# S7CAS-PLEIADES-CARTE-MERE_P02_USB.net
KiCad netlist of a schematic drawn in Altium Designer
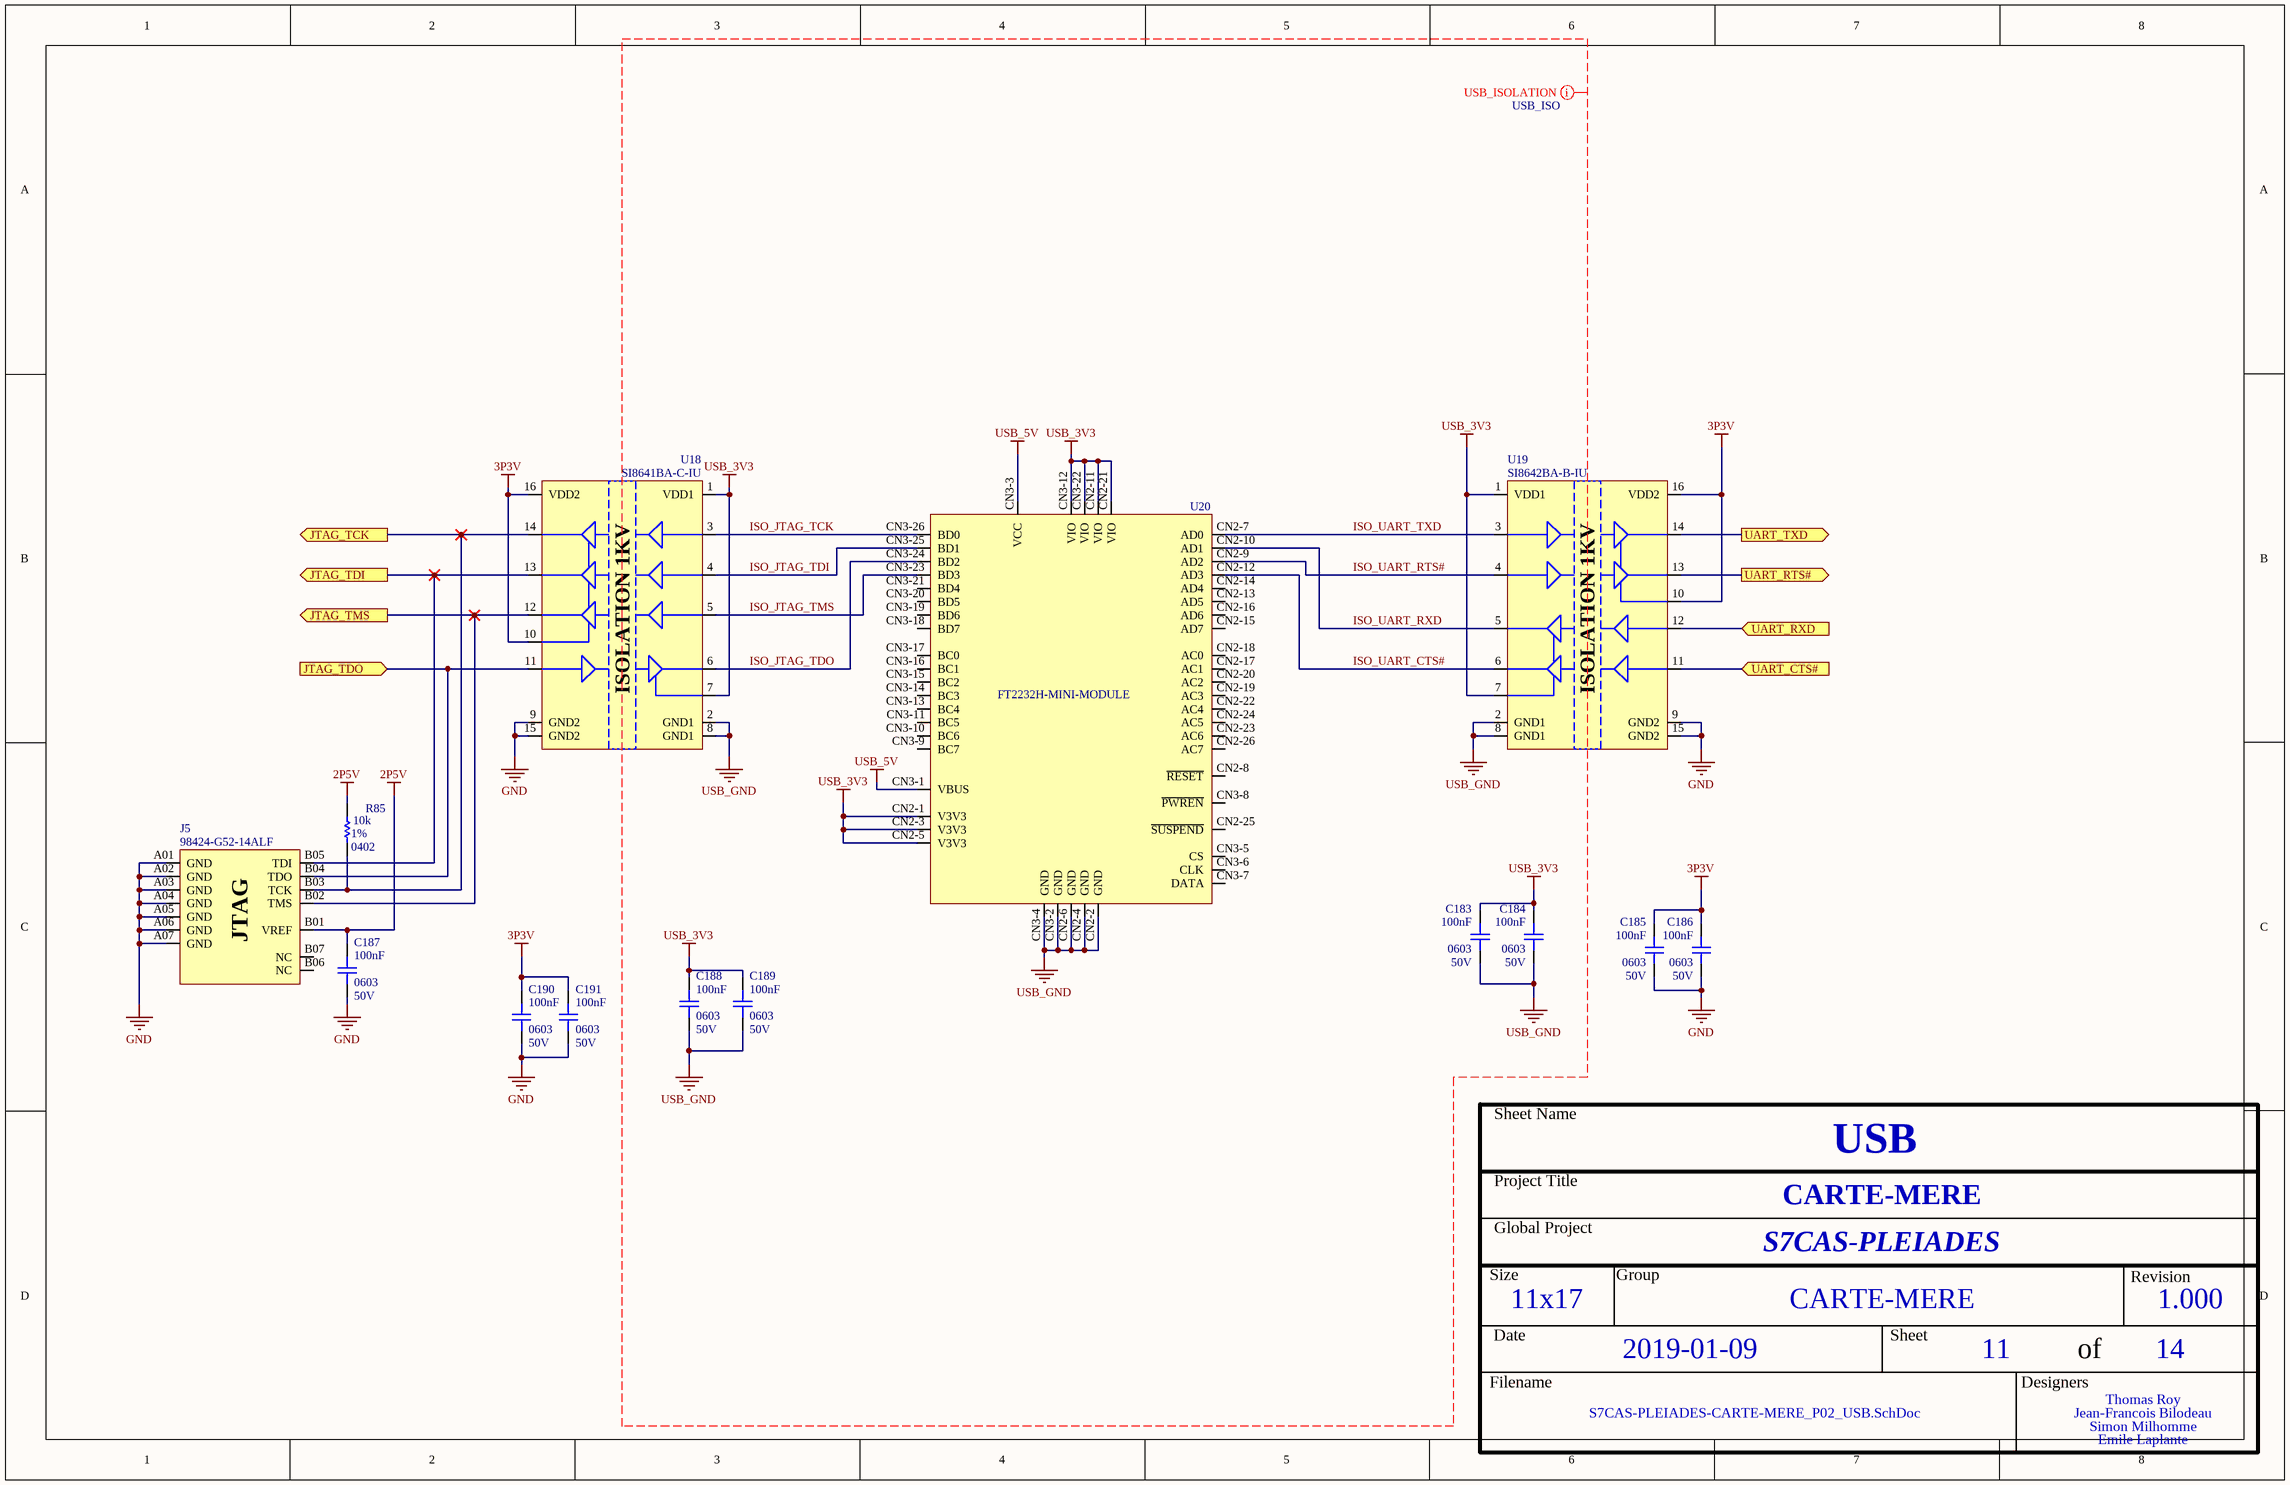
[diagram p0: S7CAS-PLEIADES-CARTE-MERE_P02_USB.SchDoc]

(export (version "E")
  (design (tool "Eeschema 10.0.6"))
  (components
    (comp (ref "C183")
      (value "100nF")
      (footprint "CAP_0603")
      (description "CAP - 0603")
      (fields
        (field (name "VOLTAGE") "50V")
        (field (name "PACKAGE") "0603")
        (field (name "CREATEDBY") "Jonathan Bouchard")
      )
      (libsource (lib "S7CAS_Lib2019_REV1_00") (part "CAP - 0603"))
    )
    (comp (ref "C184")
      (value "100nF")
      (footprint "CAP_0603")
      (description "CAP - 0603")
      (fields
        (field (name "VOLTAGE") "50V")
        (field (name "PACKAGE") "0603")
        (field (name "CREATEDBY") "Jonathan Bouchard")
      )
      (libsource (lib "S7CAS_Lib2019_REV1_00") (part "CAP - 0603"))
    )
    (comp (ref "C185")
      (value "100nF")
      (footprint "CAP_0603")
      (description "CAP - 0603")
      (fields
        (field (name "VOLTAGE") "50V")
        (field (name "PACKAGE") "0603")
        (field (name "CREATEDBY") "Jonathan Bouchard")
      )
      (libsource (lib "S7CAS_Lib2019_REV1_00") (part "CAP - 0603"))
    )
    (comp (ref "C186")
      (value "100nF")
      (footprint "CAP_0603")
      (description "CAP - 0603")
      (fields
        (field (name "VOLTAGE") "50V")
        (field (name "PACKAGE") "0603")
        (field (name "CREATEDBY") "Jonathan Bouchard")
      )
      (libsource (lib "S7CAS_Lib2019_REV1_00") (part "CAP - 0603"))
    )
    (comp (ref "C187")
      (value "100nF")
      (footprint "CAP_0603")
      (description "CAP - 0603")
      (fields
        (field (name "VOLTAGE") "50V")
        (field (name "PACKAGE") "0603")
        (field (name "CREATEDBY") "Jonathan Bouchard")
      )
      (libsource (lib "S7CAS_Lib2019_REV1_00") (part "CAP - 0603"))
    )
    (comp (ref "C188")
      (value "100nF")
      (footprint "CAP_0603")
      (description "CAP - 0603")
      (fields
        (field (name "VOLTAGE") "50V")
        (field (name "PACKAGE") "0603")
        (field (name "CREATEDBY") "Jonathan Bouchard")
      )
      (libsource (lib "S7CAS_Lib2019_REV1_00") (part "CAP - 0603"))
    )
    (comp (ref "C189")
      (value "100nF")
      (footprint "CAP_0603")
      (description "CAP - 0603")
      (fields
        (field (name "VOLTAGE") "50V")
        (field (name "PACKAGE") "0603")
        (field (name "CREATEDBY") "Jonathan Bouchard")
      )
      (libsource (lib "S7CAS_Lib2019_REV1_00") (part "CAP - 0603"))
    )
    (comp (ref "C190")
      (value "100nF")
      (footprint "CAP_0603")
      (description "CAP - 0603")
      (fields
        (field (name "VOLTAGE") "50V")
        (field (name "PACKAGE") "0603")
        (field (name "CREATEDBY") "Jonathan Bouchard")
      )
      (libsource (lib "S7CAS_Lib2019_REV1_00") (part "CAP - 0603"))
    )
    (comp (ref "C191")
      (value "100nF")
      (footprint "CAP_0603")
      (description "CAP - 0603")
      (fields
        (field (name "VOLTAGE") "50V")
        (field (name "PACKAGE") "0603")
        (field (name "CREATEDBY") "Jonathan Bouchard")
      )
      (libsource (lib "S7CAS_Lib2019_REV1_00") (part "CAP - 0603"))
    )
    (comp (ref "J5")
      (value "98424-G52-14ALF")
      (footprint "CON_JTAG_98424-G52-14ALF")
      (description "CONN -  JTAG HEADER XILINX - 14-SMD")
      (fields (field (name "MFG") "Amphenol") (field (name "CREATEDBY") "Jonathan Bouchard"))
      (libsource (lib "S7CAS_Lib2019_REV1_00") (part "CONN_JTAG_98424-G52-14ALF"))
    )
    (comp (ref "R85")
      (value "10k")
      (footprint "RES_0402")
      (description "RES - 0402")
      (fields
        (field (name "VOLTAGE") "50V")
        (field (name "POWER") "1/16W")
        (field (name "PACKAGE") "0402")
        (field (name "PRECISION") "1%")
        (field (name "CREATEDBY") "Jonathan Bouchard")
      )
      (libsource (lib "S7CAS_Lib2019_REV1_00") (part "RES - 0402"))
    )
    (comp (ref "U18")
      (value "SI8641BA-C-IU")
      (footprint "ISO_SI8642BA-B-IU")
      (description "ISO - DIGITAL ISOLATOR 1KV 4CH 3:1 GEN PURP -  SOP-16")
      (fields
        (field (name "VOLTAGE") "2.5 V ~ 5.5 V")
        (field (name "MFG") "Silicon Labs")
        (field (name "CREATEDBY") "Jonathan Bouchard")
      )
      (libsource (lib "S7CAS_Lib2019_REV1_00") (part "ISO_SI8641BA-C-IU"))
    )
    (comp (ref "U19")
      (value "SI8642BA-B-IU")
      (footprint "ISO_SI8642BA-B-IU")
      (description "ISO - DIGITAL ISOLATOR 1KV 4CH 2:2 GEN PURP -  SOP-16")
      (fields
        (field (name "VOLTAGE") "2.5 V ~ 5.5 V")
        (field (name "MFG") "Silicon Labs")
        (field (name "CREATEDBY") "Jonathan Bouchard")
      )
      (libsource (lib "S7CAS_Lib2019_REV1_00") (part "ISO_SI8642BA-B-IU"))
    )
    (comp (ref "U20")
      (value "FT2232H-MINI-MODULE")
      (footprint "COM_USB_FT2232H-MINI-MODULE")
      (description "COM - USB FTDI FT2232H Mini-Module - TH")
      (fields (field (name "MFG") "Micrel") (field (name "CREATEDBY") "Jonathan Bouchard"))
      (libsource (lib "S7CAS_Lib2019_REV1_00") (part "COM_USB_FT2232H-MINI-MODULE"))
    )
  )
  (nets
    (net (code "1") (name "/ISO_JTAG_TCK") (class "Default")
      (node (ref "U18") (pin "3") (pinfunction "A1_3") (pintype "passive"))
      (node (ref "U20") (pin "CN3-26") (pinfunction "BD0_CN3-26") (pintype "passive"))
    )
    (net (code "2") (name "/ISO_JTAG_TDI") (class "Default")
      (node (ref "U18") (pin "4") (pinfunction "A2_4") (pintype "passive"))
      (node (ref "U20") (pin "CN3-25") (pinfunction "BD1_CN3-25") (pintype "passive"))
    )
    (net (code "3") (name "/ISO_JTAG_TDO") (class "Default")
      (node (ref "U18") (pin "6") (pinfunction "A4_6") (pintype "passive"))
      (node (ref "U20") (pin "CN3-24") (pinfunction "BD2_CN3-24") (pintype "passive"))
    )
    (net (code "4") (name "/ISO_JTAG_TMS") (class "Default")
      (node (ref "U18") (pin "5") (pinfunction "A3_5") (pintype "passive"))
      (node (ref "U20") (pin "CN3-23") (pinfunction "BD3_CN3-23") (pintype "passive"))
    )
    (net (code "5") (name "/ISO_UART_CTS#") (class "Default")
      (node (ref "U19") (pin "6") (pinfunction "A4_6") (pintype "passive"))
      (node (ref "U20") (pin "CN2-12") (pinfunction "AD3_CN2-12") (pintype "passive"))
    )
    (net (code "6") (name "/ISO_UART_RTS#") (class "Default")
      (node (ref "U19") (pin "4") (pinfunction "A2_4") (pintype "passive"))
      (node (ref "U20") (pin "CN2-9") (pinfunction "AD2_CN2-9") (pintype "passive"))
    )
    (net (code "7") (name "/ISO_UART_RXD") (class "Default")
      (node (ref "U19") (pin "5") (pinfunction "A3_5") (pintype "passive"))
      (node (ref "U20") (pin "CN2-10") (pinfunction "AD1_CN2-10") (pintype "passive"))
    )
    (net (code "8") (name "/ISO_UART_TXD") (class "Default")
      (node (ref "U19") (pin "3") (pinfunction "A1_3") (pintype "passive"))
      (node (ref "U20") (pin "CN2-7") (pinfunction "AD0_CN2-7") (pintype "passive"))
    )
    (net (code "9") (name "/JTAG_TCK") (class "Default")
      (node (ref "J5") (pin "B03") (pinfunction "TCK_B03") (pintype "passive"))
      (node (ref "R85") (pin "1") (pinfunction "1_1") (pintype "passive"))
      (node (ref "U18") (pin "14") (pinfunction "B1_14") (pintype "passive"))
    )
    (net (code "10") (name "/JTAG_TDI") (class "Default")
      (node (ref "J5") (pin "B05") (pinfunction "TDI_B05") (pintype "passive"))
      (node (ref "U18") (pin "13") (pinfunction "B2_13") (pintype "passive"))
    )
    (net (code "11") (name "/JTAG_TDO") (class "Default")
      (node (ref "J5") (pin "B04") (pinfunction "TDO_B04") (pintype "passive"))
      (node (ref "U18") (pin "11") (pinfunction "B4_11") (pintype "passive"))
    )
    (net (code "12") (name "/JTAG_TMS") (class "Default")
      (node (ref "J5") (pin "B02") (pinfunction "TMS_B02") (pintype "passive"))
      (node (ref "U18") (pin "12") (pinfunction "B3_12") (pintype "passive"))
    )
    (net (code "13") (name "/UART_CTS#") (class "Default")
      (node (ref "U19") (pin "11") (pinfunction "B4_11") (pintype "passive"))
    )
    (net (code "14") (name "/UART_RTS#") (class "Default")
      (node (ref "U19") (pin "13") (pinfunction "B2_13") (pintype "passive"))
    )
    (net (code "15") (name "/UART_RXD") (class "Default")
      (node (ref "U19") (pin "12") (pinfunction "B3_12") (pintype "passive"))
    )
    (net (code "16") (name "/UART_TXD") (class "Default")
      (node (ref "U19") (pin "14") (pinfunction "B1_14") (pintype "passive"))
    )
    (net (code "17") (name "2P5V") (class "Default")
      (node (ref "C187") (pin "2") (pinfunction "2_2") (pintype "passive"))
      (node (ref "J5") (pin "B01") (pinfunction "VREF_B01") (pintype "passive"))
      (node (ref "R85") (pin "2") (pinfunction "2_2") (pintype "passive"))
    )
    (net (code "18") (name "3P3V") (class "Default")
      (node (ref "C185") (pin "2") (pinfunction "2_2") (pintype "passive"))
      (node (ref "C186") (pin "2") (pinfunction "2_2") (pintype "passive"))
      (node (ref "C190") (pin "2") (pinfunction "2_2") (pintype "passive"))
      (node (ref "C191") (pin "2") (pinfunction "2_2") (pintype "passive"))
      (node (ref "U18") (pin "10") (pinfunction "EN2_10") (pintype "passive"))
      (node (ref "U18") (pin "16") (pinfunction "VDD2_16") (pintype "power_in"))
      (node (ref "U19") (pin "10") (pinfunction "EN2_10") (pintype "passive"))
      (node (ref "U19") (pin "16") (pinfunction "VDD2_16") (pintype "power_in"))
    )
    (net (code "19") (name "GND") (class "Default")
      (node (ref "C185") (pin "1") (pinfunction "1_1") (pintype "passive"))
      (node (ref "C186") (pin "1") (pinfunction "1_1") (pintype "passive"))
      (node (ref "C187") (pin "1") (pinfunction "1_1") (pintype "passive"))
      (node (ref "C190") (pin "1") (pinfunction "1_1") (pintype "passive"))
      (node (ref "C191") (pin "1") (pinfunction "1_1") (pintype "passive"))
      (node (ref "J5") (pin "A01") (pinfunction "GND_A01") (pintype "passive"))
      (node (ref "J5") (pin "A02") (pinfunction "GND_A02") (pintype "passive"))
      (node (ref "J5") (pin "A03") (pinfunction "GND_A03") (pintype "passive"))
      (node (ref "J5") (pin "A04") (pinfunction "GND_A04") (pintype "passive"))
      (node (ref "J5") (pin "A05") (pinfunction "GND_A05") (pintype "passive"))
      (node (ref "J5") (pin "A06") (pinfunction "GND_A06") (pintype "passive"))
      (node (ref "J5") (pin "A07") (pinfunction "GND_A07") (pintype "passive"))
      (node (ref "U18") (pin "15") (pinfunction "GND2_15") (pintype "passive"))
      (node (ref "U18") (pin "9") (pinfunction "GND2_9") (pintype "passive"))
      (node (ref "U19") (pin "15") (pinfunction "GND2_15") (pintype "passive"))
      (node (ref "U19") (pin "9") (pinfunction "GND2_9") (pintype "passive"))
    )
    (net (code "20") (name "USB_3V3") (class "Default")
      (node (ref "C183") (pin "2") (pinfunction "2_2") (pintype "passive"))
      (node (ref "C184") (pin "2") (pinfunction "2_2") (pintype "passive"))
      (node (ref "C188") (pin "2") (pinfunction "2_2") (pintype "passive"))
      (node (ref "C189") (pin "2") (pinfunction "2_2") (pintype "passive"))
      (node (ref "U18") (pin "1") (pinfunction "VDD1_1") (pintype "power_in"))
      (node (ref "U18") (pin "7") (pinfunction "EN1_7") (pintype "passive"))
      (node (ref "U19") (pin "1") (pinfunction "VDD1_1") (pintype "power_in"))
      (node (ref "U19") (pin "7") (pinfunction "EN1_7") (pintype "passive"))
      (node (ref "U20") (pin "CN2-1") (pinfunction "V3V3_CN2-1") (pintype "power_in"))
      (node (ref "U20") (pin "CN2-11") (pinfunction "VIO_CN2-11") (pintype "passive"))
      (node (ref "U20") (pin "CN2-21") (pinfunction "VIO_CN2-21") (pintype "passive"))
      (node (ref "U20") (pin "CN2-3") (pinfunction "V3V3_CN2-3") (pintype "power_in"))
      (node (ref "U20") (pin "CN2-5") (pinfunction "V3V3_CN2-5") (pintype "power_in"))
      (node (ref "U20") (pin "CN3-12") (pinfunction "VIO_CN3-12") (pintype "passive"))
      (node (ref "U20") (pin "CN3-22") (pinfunction "VIO_CN3-22") (pintype "passive"))
    )
    (net (code "21") (name "USB_5V") (class "Default")
      (node (ref "U20") (pin "CN3-1") (pinfunction "VBUS_CN3-1") (pintype "passive"))
      (node (ref "U20") (pin "CN3-3") (pinfunction "VCC_CN3-3") (pintype "power_in"))
    )
    (net (code "22") (name "USB_GND") (class "Default")
      (node (ref "C183") (pin "1") (pinfunction "1_1") (pintype "passive"))
      (node (ref "C184") (pin "1") (pinfunction "1_1") (pintype "passive"))
      (node (ref "C188") (pin "1") (pinfunction "1_1") (pintype "passive"))
      (node (ref "C189") (pin "1") (pinfunction "1_1") (pintype "passive"))
      (node (ref "U18") (pin "2") (pinfunction "GND1_2") (pintype "passive"))
      (node (ref "U18") (pin "8") (pinfunction "GND1_8") (pintype "passive"))
      (node (ref "U19") (pin "2") (pinfunction "GND1_2") (pintype "passive"))
      (node (ref "U19") (pin "8") (pinfunction "GND1_8") (pintype "passive"))
      (node (ref "U20") (pin "CN2-2") (pinfunction "GND_CN2-2") (pintype "passive"))
      (node (ref "U20") (pin "CN2-4") (pinfunction "GND_CN2-4") (pintype "passive"))
      (node (ref "U20") (pin "CN2-6") (pinfunction "GND_CN2-6") (pintype "passive"))
      (node (ref "U20") (pin "CN3-2") (pinfunction "GND_CN3-2") (pintype "passive"))
      (node (ref "U20") (pin "CN3-4") (pinfunction "GND_CN3-4") (pintype "passive"))
    )
    (net (code "23") (name "unconnected-(J5-NC-PadB06)") (class "Default")
      (node (ref "J5") (pin "B06") (pinfunction "NC_B06") (pintype "passive"))
    )
    (net (code "24") (name "unconnected-(J5-NC-PadB07)") (class "Default")
      (node (ref "J5") (pin "B07") (pinfunction "NC_B07") (pintype "passive"))
    )
    (net (code "25") (name "unconnected-(U20-AC0-PadCN2-18)") (class "Default")
      (node (ref "U20") (pin "CN2-18") (pinfunction "AC0_CN2-18") (pintype "passive"))
    )
    (net (code "26") (name "unconnected-(U20-AC1-PadCN2-17)") (class "Default")
      (node (ref "U20") (pin "CN2-17") (pinfunction "AC1_CN2-17") (pintype "passive"))
    )
    (net (code "27") (name "unconnected-(U20-AC2-PadCN2-20)") (class "Default")
      (node (ref "U20") (pin "CN2-20") (pinfunction "AC2_CN2-20") (pintype "passive"))
    )
    (net (code "28") (name "unconnected-(U20-AC3-PadCN2-19)") (class "Default")
      (node (ref "U20") (pin "CN2-19") (pinfunction "AC3_CN2-19") (pintype "passive"))
    )
    (net (code "29") (name "unconnected-(U20-AC4-PadCN2-22)") (class "Default")
      (node (ref "U20") (pin "CN2-22") (pinfunction "AC4_CN2-22") (pintype "passive"))
    )
    (net (code "30") (name "unconnected-(U20-AC5-PadCN2-24)") (class "Default")
      (node (ref "U20") (pin "CN2-24") (pinfunction "AC5_CN2-24") (pintype "passive"))
    )
    (net (code "31") (name "unconnected-(U20-AC6-PadCN2-23)") (class "Default")
      (node (ref "U20") (pin "CN2-23") (pinfunction "AC6_CN2-23") (pintype "passive"))
    )
    (net (code "32") (name "unconnected-(U20-AC7-PadCN2-26)") (class "Default")
      (node (ref "U20") (pin "CN2-26") (pinfunction "AC7_CN2-26") (pintype "passive"))
    )
    (net (code "33") (name "unconnected-(U20-AD4-PadCN2-14)") (class "Default")
      (node (ref "U20") (pin "CN2-14") (pinfunction "AD4_CN2-14") (pintype "passive"))
    )
    (net (code "34") (name "unconnected-(U20-AD5-PadCN2-13)") (class "Default")
      (node (ref "U20") (pin "CN2-13") (pinfunction "AD5_CN2-13") (pintype "passive"))
    )
    (net (code "35") (name "unconnected-(U20-AD6-PadCN2-16)") (class "Default")
      (node (ref "U20") (pin "CN2-16") (pinfunction "AD6_CN2-16") (pintype "passive"))
    )
    (net (code "36") (name "unconnected-(U20-AD7-PadCN2-15)") (class "Default")
      (node (ref "U20") (pin "CN2-15") (pinfunction "AD7_CN2-15") (pintype "passive"))
    )
    (net (code "37") (name "unconnected-(U20-BC0-PadCN3-17)") (class "Default")
      (node (ref "U20") (pin "CN3-17") (pinfunction "BC0_CN3-17") (pintype "passive"))
    )
    (net (code "38") (name "unconnected-(U20-BC1-PadCN3-16)") (class "Default")
      (node (ref "U20") (pin "CN3-16") (pinfunction "BC1_CN3-16") (pintype "passive"))
    )
    (net (code "39") (name "unconnected-(U20-BC2-PadCN3-15)") (class "Default")
      (node (ref "U20") (pin "CN3-15") (pinfunction "BC2_CN3-15") (pintype "passive"))
    )
    (net (code "40") (name "unconnected-(U20-BC3-PadCN3-14)") (class "Default")
      (node (ref "U20") (pin "CN3-14") (pinfunction "BC3_CN3-14") (pintype "passive"))
    )
    (net (code "41") (name "unconnected-(U20-BC4-PadCN3-13)") (class "Default")
      (node (ref "U20") (pin "CN3-13") (pinfunction "BC4_CN3-13") (pintype "passive"))
    )
    (net (code "42") (name "unconnected-(U20-BC5-PadCN3-11)") (class "Default")
      (node (ref "U20") (pin "CN3-11") (pinfunction "BC5_CN3-11") (pintype "passive"))
    )
    (net (code "43") (name "unconnected-(U20-BC6-PadCN3-10)") (class "Default")
      (node (ref "U20") (pin "CN3-10") (pinfunction "BC6_CN3-10") (pintype "passive"))
    )
    (net (code "44") (name "unconnected-(U20-BC7-PadCN3-9)") (class "Default")
      (node (ref "U20") (pin "CN3-9") (pinfunction "BC7_CN3-9") (pintype "passive"))
    )
    (net (code "45") (name "unconnected-(U20-BD4-PadCN3-21)") (class "Default")
      (node (ref "U20") (pin "CN3-21") (pinfunction "BD4_CN3-21") (pintype "passive"))
    )
    (net (code "46") (name "unconnected-(U20-BD5-PadCN3-20)") (class "Default")
      (node (ref "U20") (pin "CN3-20") (pinfunction "BD5_CN3-20") (pintype "passive"))
    )
    (net (code "47") (name "unconnected-(U20-BD6-PadCN3-19)") (class "Default")
      (node (ref "U20") (pin "CN3-19") (pinfunction "BD6_CN3-19") (pintype "passive"))
    )
    (net (code "48") (name "unconnected-(U20-BD7-PadCN3-18)") (class "Default")
      (node (ref "U20") (pin "CN3-18") (pinfunction "BD7_CN3-18") (pintype "passive"))
    )
    (net (code "49") (name "unconnected-(U20-CLK-PadCN3-6)") (class "Default")
      (node (ref "U20") (pin "CN3-6") (pinfunction "CLK_CN3-6") (pintype "passive"))
    )
    (net (code "50") (name "unconnected-(U20-CS-PadCN3-5)") (class "Default")
      (node (ref "U20") (pin "CN3-5") (pinfunction "CS_CN3-5") (pintype "passive"))
    )
    (net (code "51") (name "unconnected-(U20-DATA-PadCN3-7)") (class "Default")
      (node (ref "U20") (pin "CN3-7") (pinfunction "DATA_CN3-7") (pintype "passive"))
    )
    (net (code "52") (name "unconnected-(U20-PWREN-PadCN3-8)") (class "Default")
      (node (ref "U20") (pin "CN3-8") (pinfunction "PWREN_CN3-8") (pintype "passive"))
    )
    (net (code "53") (name "unconnected-(U20-RESET-PadCN2-8)") (class "Default")
      (node (ref "U20") (pin "CN2-8") (pinfunction "RESET_CN2-8") (pintype "passive"))
    )
    (net (code "54") (name "unconnected-(U20-SUSPEND-PadCN2-25)") (class "Default")
      (node (ref "U20") (pin "CN2-25") (pinfunction "SUSPEND_CN2-25") (pintype "passive"))
    )
  )
)
